# BMduino_test.net
KiCad netlist of a schematic drawn in Altium Designer
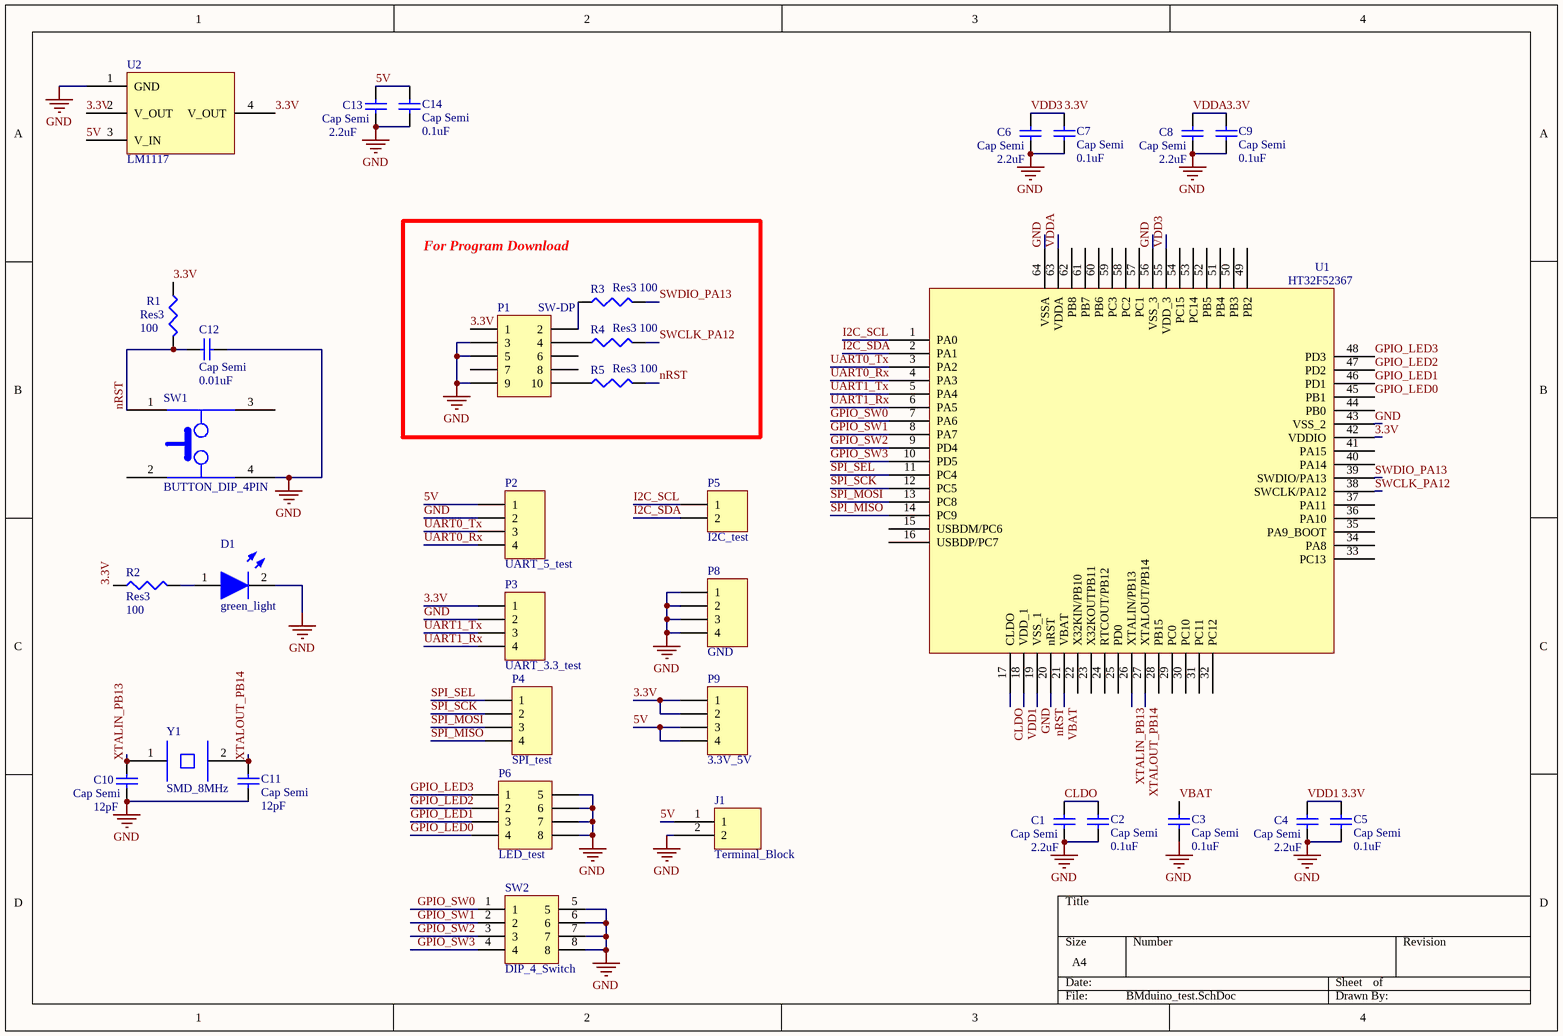
[diagram p0: BMduino_test.SchDoc]

(export (version "E")
  (design (tool "Eeschema 10.0.6"))
  (components
    (comp (ref "C1")
      (value "Cap Semi")
      (footprint "1608[0603]")
      (description "Capacitor (Semiconductor SIM Model)")
      (fields (field (name "ALTIUM_VALUE") "2.2uF") (field (name "PUBLISHER") "Altium Limited"))
      (libsource (lib "Miscellaneous Devices") (part "Cap Semi"))
    )
    (comp (ref "C2")
      (value "Cap Semi")
      (footprint "1608[0603]")
      (description "Capacitor (Semiconductor SIM Model)")
      (fields (field (name "ALTIUM_VALUE") "0.1uF") (field (name "PUBLISHER") "Altium Limited"))
      (libsource (lib "Miscellaneous Devices") (part "Cap Semi"))
    )
    (comp (ref "C3")
      (value "Cap Semi")
      (footprint "1608[0603]")
      (description "Capacitor (Semiconductor SIM Model)")
      (fields (field (name "ALTIUM_VALUE") "0.1uF") (field (name "PUBLISHER") "Altium Limited"))
      (libsource (lib "Miscellaneous Devices") (part "Cap Semi"))
    )
    (comp (ref "C4")
      (value "Cap Semi")
      (footprint "1608[0603]")
      (description "Capacitor (Semiconductor SIM Model)")
      (fields (field (name "ALTIUM_VALUE") "2.2uF") (field (name "PUBLISHER") "Altium Limited"))
      (libsource (lib "Miscellaneous Devices") (part "Cap Semi"))
    )
    (comp (ref "C5")
      (value "Cap Semi")
      (footprint "1608[0603]")
      (description "Capacitor (Semiconductor SIM Model)")
      (fields (field (name "ALTIUM_VALUE") "0.1uF") (field (name "PUBLISHER") "Altium Limited"))
      (libsource (lib "Miscellaneous Devices") (part "Cap Semi"))
    )
    (comp (ref "C6")
      (value "Cap Semi")
      (footprint "1608[0603]")
      (description "Capacitor (Semiconductor SIM Model)")
      (fields (field (name "ALTIUM_VALUE") "2.2uF") (field (name "PUBLISHER") "Altium Limited"))
      (libsource (lib "Miscellaneous Devices") (part "Cap Semi"))
    )
    (comp (ref "C7")
      (value "Cap Semi")
      (footprint "1608[0603]")
      (description "Capacitor (Semiconductor SIM Model)")
      (fields (field (name "ALTIUM_VALUE") "0.1uF") (field (name "PUBLISHER") "Altium Limited"))
      (libsource (lib "Miscellaneous Devices") (part "Cap Semi"))
    )
    (comp (ref "C8")
      (value "Cap Semi")
      (footprint "1608[0603]")
      (description "Capacitor (Semiconductor SIM Model)")
      (fields (field (name "ALTIUM_VALUE") "2.2uF") (field (name "PUBLISHER") "Altium Limited"))
      (libsource (lib "Miscellaneous Devices") (part "Cap Semi"))
    )
    (comp (ref "C9")
      (value "Cap Semi")
      (footprint "1608[0603]")
      (description "Capacitor (Semiconductor SIM Model)")
      (fields (field (name "ALTIUM_VALUE") "0.1uF") (field (name "PUBLISHER") "Altium Limited"))
      (libsource (lib "Miscellaneous Devices") (part "Cap Semi"))
    )
    (comp (ref "C10")
      (value "Cap Semi")
      (footprint "1608[0603]")
      (description "Capacitor (Semiconductor SIM Model)")
      (fields (field (name "ALTIUM_VALUE") "12pF") (field (name "PUBLISHER") "Altium Limited"))
      (libsource (lib "Miscellaneous Devices") (part "Cap Semi"))
    )
    (comp (ref "C11")
      (value "Cap Semi")
      (footprint "1608[0603]")
      (description "Capacitor (Semiconductor SIM Model)")
      (fields (field (name "ALTIUM_VALUE") "12pF") (field (name "PUBLISHER") "Altium Limited"))
      (libsource (lib "Miscellaneous Devices") (part "Cap Semi"))
    )
    (comp (ref "C12")
      (value "Cap Semi")
      (footprint "1608[0603]")
      (description "Capacitor (Semiconductor SIM Model)")
      (fields (field (name "ALTIUM_VALUE") "0.01uF") (field (name "PUBLISHER") "Altium Limited"))
      (libsource (lib "Miscellaneous Devices") (part "Cap Semi"))
    )
    (comp (ref "C13")
      (value "Cap Semi")
      (footprint "1608[0603]")
      (description "Capacitor (Semiconductor SIM Model)")
      (fields (field (name "ALTIUM_VALUE") "2.2uF") (field (name "PUBLISHER") "Altium Limited"))
      (libsource (lib "Miscellaneous Devices") (part "Cap Semi"))
    )
    (comp (ref "C14")
      (value "Cap Semi")
      (footprint "1608[0603]")
      (description "Capacitor (Semiconductor SIM Model)")
      (fields (field (name "ALTIUM_VALUE") "0.1uF") (field (name "PUBLISHER") "Altium Limited"))
      (libsource (lib "Miscellaneous Devices") (part "Cap Semi"))
    )
    (comp (ref "D1")
      (value "green_light")
      (footprint "LED_Green")
      (libsource (lib "Lab_share") (part "LED_Green"))
    )
    (comp (ref "J1")
      (value "Terminal_Block")
      (footprint "terminal block")
      (libsource (lib "Lab_share") (part "Terminal Block"))
    )
    (comp (ref "P1")
      (value "SW-DP")
      (footprint "HDR2X5")
      (description "Header, 5-Pin, Dual row")
      (fields (field (name "PUBLISHER") "Altium Limited"))
      (libsource (lib "Miscellaneous Connectors") (part "Header 5X2"))
    )
    (comp (ref "P2")
      (value "UART_5_test")
      (footprint "HDR1X4")
      (description "Header, 4-Pin")
      (fields (field (name "PUBLISHER") "Altium Limited"))
      (libsource (lib "Miscellaneous Connectors") (part "Header 4"))
    )
    (comp (ref "P3")
      (value "UART_3.3_test")
      (footprint "HDR1X4")
      (description "Header, 4-Pin")
      (fields (field (name "PUBLISHER") "Altium Limited"))
      (libsource (lib "Miscellaneous Connectors") (part "Header 4"))
    )
    (comp (ref "P4")
      (value "SPI_test")
      (footprint "HDR1X4")
      (description "Header, 4-Pin")
      (fields (field (name "PUBLISHER") "Altium Limited"))
      (libsource (lib "Miscellaneous Connectors") (part "Header 4"))
    )
    (comp (ref "P5")
      (value "I2C_test")
      (footprint "HDR1X2")
      (description "Header, 2-Pin")
      (fields (field (name "PUBLISHER") "Altium Limited"))
      (libsource (lib "Miscellaneous Connectors") (part "Header 2"))
    )
    (comp (ref "P6")
      (value "LED_test")
      (footprint "HDR2X4_CEN")
      (description "Header, 4-Pin, Dual row")
      (fields (field (name "PUBLISHER") "Altium Limited"))
      (libsource (lib "Miscellaneous Connectors") (part "Header 4X2A"))
    )
    (comp (ref "P8")
      (value "GND")
      (footprint "HDR1X4")
      (description "Header, 4-Pin")
      (fields (field (name "PUBLISHER") "Altium Limited"))
      (libsource (lib "Miscellaneous Connectors") (part "Header 4"))
    )
    (comp (ref "P9")
      (value "3.3V_5V")
      (footprint "HDR1X4")
      (description "Header, 4-Pin")
      (fields (field (name "PUBLISHER") "Altium Limited"))
      (libsource (lib "Miscellaneous Connectors") (part "Header 4"))
    )
    (comp (ref "R1")
      (value "Res3")
      (footprint "J1-0603")
      (description "Resistor")
      (fields (field (name "ALTIUM_VALUE") "100") (field (name "PUBLISHER") "Altium Limited"))
      (libsource (lib "Miscellaneous Devices") (part "Res3"))
    )
    (comp (ref "R2")
      (value "Res3")
      (footprint "J1-0603")
      (description "Resistor")
      (fields (field (name "ALTIUM_VALUE") "100") (field (name "PUBLISHER") "Altium Limited"))
      (libsource (lib "Miscellaneous Devices") (part "Res3"))
    )
    (comp (ref "R3")
      (value "Res3")
      (footprint "J1-0603")
      (description "Resistor")
      (fields (field (name "ALTIUM_VALUE") "100") (field (name "PUBLISHER") "Altium Limited"))
      (libsource (lib "Miscellaneous Devices") (part "Res3"))
    )
    (comp (ref "R4")
      (value "Res3")
      (footprint "J1-0603")
      (description "Resistor")
      (fields (field (name "ALTIUM_VALUE") "100") (field (name "PUBLISHER") "Altium Limited"))
      (libsource (lib "Miscellaneous Devices") (part "Res3"))
    )
    (comp (ref "R5")
      (value "Res3")
      (footprint "J1-0603")
      (description "Resistor")
      (fields (field (name "ALTIUM_VALUE") "100") (field (name "PUBLISHER") "Altium Limited"))
      (libsource (lib "Miscellaneous Devices") (part "Res3"))
    )
    (comp (ref "SW1")
      (value "BUTTON_DIP_4PIN")
      (footprint "Push_Button")
      (libsource (lib "Lab_share") (part "Push_Button"))
    )
    (comp (ref "SW2")
      (value "DIP_4_Switch")
      (footprint "Switch_4")
      (libsource (lib "Lab_share") (part "Switch_4"))
    )
    (comp (ref "U1")
      (value "HT32F52367")
      (footprint "HT32H52367")
      (libsource (lib "Lab_share") (part "HT32F52367"))
    )
    (comp (ref "U2")
      (value "LM1117")
      (footprint "LM1117 - duplicate")
      (libsource (lib "Lab_share") (part "LM1117"))
    )
    (comp (ref "Y1")
      (value "SMD_8MHz")
      (footprint "Quartz-Crystal-8MHz")
      (libsource (lib "Lab_share") (part "Quartz_Crystal_8MHz"))
    )
  )
  (nets
    (net (code "1") (name "/3.3V") (class "Default")
      (node (ref "C4") (pin "1") (pinfunction "1_1") (pintype "passive"))
      (node (ref "C5") (pin "2") (pinfunction "2_2") (pintype "passive"))
      (node (ref "C6") (pin "1") (pinfunction "1_1") (pintype "passive"))
      (node (ref "C7") (pin "2") (pinfunction "2_2") (pintype "passive"))
      (node (ref "C8") (pin "1") (pinfunction "1_1") (pintype "passive"))
      (node (ref "C9") (pin "2") (pinfunction "2_2") (pintype "passive"))
      (node (ref "P1") (pin "1") (pinfunction "1_1") (pintype "passive"))
      (node (ref "P3") (pin "1") (pinfunction "1_1") (pintype "passive"))
      (node (ref "P9") (pin "1") (pinfunction "1_1") (pintype "passive"))
      (node (ref "P9") (pin "2") (pinfunction "2_2") (pintype "passive"))
      (node (ref "R1") (pin "1") (pinfunction "1_1") (pintype "passive"))
      (node (ref "R2") (pin "1") (pinfunction "1_1") (pintype "passive"))
      (node (ref "U1") (pin "18") (pinfunction "VDD_1_18") (pintype "passive"))
      (node (ref "U1") (pin "42") (pinfunction "VDDIO_42") (pintype "passive"))
      (node (ref "U1") (pin "55") (pinfunction "VDD_3_55") (pintype "passive"))
      (node (ref "U1") (pin "63") (pinfunction "VDDA_63") (pintype "passive"))
      (node (ref "U2") (pin "2") (pinfunction "V_OUT_2") (pintype "passive"))
      (node (ref "U2") (pin "4") (pinfunction "V_OUT_4") (pintype "passive"))
    )
    (net (code "2") (name "/5V") (class "Default")
      (node (ref "C13") (pin "1") (pinfunction "1_1") (pintype "passive"))
      (node (ref "C14") (pin "2") (pinfunction "2_2") (pintype "passive"))
      (node (ref "J1") (pin "1") (pinfunction "1_1") (pintype "passive"))
      (node (ref "P2") (pin "1") (pinfunction "1_1") (pintype "passive"))
      (node (ref "P9") (pin "3") (pinfunction "3_3") (pintype "passive"))
      (node (ref "P9") (pin "4") (pinfunction "4_4") (pintype "passive"))
      (node (ref "U2") (pin "3") (pinfunction "V_IN_3") (pintype "passive"))
    )
    (net (code "3") (name "/CLDO") (class "Default")
      (node (ref "C1") (pin "1") (pinfunction "1_1") (pintype "passive"))
      (node (ref "C2") (pin "2") (pinfunction "2_2") (pintype "passive"))
      (node (ref "U1") (pin "17") (pinfunction "CLDO_17") (pintype "passive"))
    )
    (net (code "4") (name "/GPIO_LED0") (class "Default")
      (node (ref "P6") (pin "4") (pinfunction "4_4") (pintype "passive"))
      (node (ref "U1") (pin "45") (pinfunction "PB1_45") (pintype "passive"))
    )
    (net (code "5") (name "/GPIO_LED1") (class "Default")
      (node (ref "P6") (pin "3") (pinfunction "3_3") (pintype "passive"))
      (node (ref "U1") (pin "46") (pinfunction "PD1_46") (pintype "passive"))
    )
    (net (code "6") (name "/GPIO_LED2") (class "Default")
      (node (ref "P6") (pin "2") (pinfunction "2_2") (pintype "passive"))
      (node (ref "U1") (pin "47") (pinfunction "PD2_47") (pintype "passive"))
    )
    (net (code "7") (name "/GPIO_LED3") (class "Default")
      (node (ref "P6") (pin "1") (pinfunction "1_1") (pintype "passive"))
      (node (ref "U1") (pin "48") (pinfunction "PD3_48") (pintype "passive"))
    )
    (net (code "8") (name "/GPIO_SW0") (class "Default")
      (node (ref "SW2") (pin "1") (pinfunction "1_1") (pintype "passive"))
      (node (ref "U1") (pin "7") (pinfunction "PA6_7") (pintype "passive"))
    )
    (net (code "9") (name "/GPIO_SW1") (class "Default")
      (node (ref "SW2") (pin "2") (pinfunction "2_2") (pintype "passive"))
      (node (ref "U1") (pin "8") (pinfunction "PA7_8") (pintype "passive"))
    )
    (net (code "10") (name "/GPIO_SW2") (class "Default")
      (node (ref "SW2") (pin "3") (pinfunction "3_3") (pintype "passive"))
      (node (ref "U1") (pin "9") (pinfunction "PD4_9") (pintype "passive"))
    )
    (net (code "11") (name "/GPIO_SW3") (class "Default")
      (node (ref "SW2") (pin "4") (pinfunction "4_4") (pintype "passive"))
      (node (ref "U1") (pin "10") (pinfunction "PD5_10") (pintype "passive"))
    )
    (net (code "12") (name "/I2C_SCL") (class "Default")
      (node (ref "P5") (pin "1") (pinfunction "1_1") (pintype "passive"))
      (node (ref "U1") (pin "1") (pinfunction "PA0_1") (pintype "passive"))
    )
    (net (code "13") (name "/I2C_SDA") (class "Default")
      (node (ref "P5") (pin "2") (pinfunction "2_2") (pintype "passive"))
      (node (ref "U1") (pin "2") (pinfunction "PA1_2") (pintype "passive"))
    )
    (net (code "14") (name "/SPI_MISO") (class "Default")
      (node (ref "P4") (pin "4") (pinfunction "4_4") (pintype "passive"))
      (node (ref "U1") (pin "14") (pinfunction "PC9_14") (pintype "passive"))
    )
    (net (code "15") (name "/SPI_MOSI") (class "Default")
      (node (ref "P4") (pin "3") (pinfunction "3_3") (pintype "passive"))
      (node (ref "U1") (pin "13") (pinfunction "PC8_13") (pintype "passive"))
    )
    (net (code "16") (name "/SPI_SCK") (class "Default")
      (node (ref "P4") (pin "2") (pinfunction "2_2") (pintype "passive"))
      (node (ref "U1") (pin "12") (pinfunction "PC5_12") (pintype "passive"))
    )
    (net (code "17") (name "/SPI_SEL") (class "Default")
      (node (ref "P4") (pin "1") (pinfunction "1_1") (pintype "passive"))
      (node (ref "U1") (pin "11") (pinfunction "PC4_11") (pintype "passive"))
    )
    (net (code "18") (name "/SWCLK_PA12") (class "Default")
      (node (ref "R4") (pin "2") (pinfunction "2_2") (pintype "passive"))
      (node (ref "U1") (pin "38") (pinfunction "SWCLK/PA12_38") (pintype "passive"))
    )
    (net (code "19") (name "/SWDIO_PA13") (class "Default")
      (node (ref "R3") (pin "2") (pinfunction "2_2") (pintype "passive"))
      (node (ref "U1") (pin "39") (pinfunction "SWDIO/PA13_39") (pintype "passive"))
    )
    (net (code "20") (name "/UART0_Rx") (class "Default")
      (node (ref "P2") (pin "4") (pinfunction "4_4") (pintype "passive"))
      (node (ref "U1") (pin "4") (pinfunction "PA3_4") (pintype "passive"))
    )
    (net (code "21") (name "/UART0_Tx") (class "Default")
      (node (ref "P2") (pin "3") (pinfunction "3_3") (pintype "passive"))
      (node (ref "U1") (pin "3") (pinfunction "PA2_3") (pintype "passive"))
    )
    (net (code "22") (name "/UART1_Rx") (class "Default")
      (node (ref "P3") (pin "4") (pinfunction "4_4") (pintype "passive"))
      (node (ref "U1") (pin "6") (pinfunction "PA5_6") (pintype "passive"))
    )
    (net (code "23") (name "/UART1_Tx") (class "Default")
      (node (ref "P3") (pin "3") (pinfunction "3_3") (pintype "passive"))
      (node (ref "U1") (pin "5") (pinfunction "PA4_5") (pintype "passive"))
    )
    (net (code "24") (name "/VBAT") (class "Default")
      (node (ref "C3") (pin "2") (pinfunction "2_2") (pintype "passive"))
      (node (ref "U1") (pin "21") (pinfunction "VBAT_21") (pintype "passive"))
    )
    (net (code "25") (name "/XTALIN_PB13") (class "Default")
      (node (ref "C10") (pin "1") (pinfunction "1_1") (pintype "passive"))
      (node (ref "U1") (pin "26") (pinfunction "XTALIN/PB13_26") (pintype "passive"))
      (node (ref "Y1") (pin "1") (pintype "passive"))
    )
    (net (code "26") (name "/XTALOUT_PB14") (class "Default")
      (node (ref "C11") (pin "2") (pinfunction "2_2") (pintype "passive"))
      (node (ref "U1") (pin "27") (pinfunction "XTALOUT/PB14_27") (pintype "passive"))
      (node (ref "Y1") (pin "2") (pintype "passive"))
    )
    (net (code "27") (name "/nRST") (class "Default")
      (node (ref "C12") (pin "2") (pinfunction "2_2") (pintype "passive"))
      (node (ref "R1") (pin "2") (pinfunction "2_2") (pintype "passive"))
      (node (ref "R5") (pin "2") (pinfunction "2_2") (pintype "passive"))
      (node (ref "SW1") (pin "1") (pintype "passive"))
      (node (ref "U1") (pin "20") (pinfunction "nRST_20") (pintype "passive"))
    )
    (net (code "28") (name "GND") (class "Default")
      (node (ref "C1") (pin "2") (pinfunction "2_2") (pintype "passive"))
      (node (ref "C10") (pin "2") (pinfunction "2_2") (pintype "passive"))
      (node (ref "C11") (pin "1") (pinfunction "1_1") (pintype "passive"))
      (node (ref "C12") (pin "1") (pinfunction "1_1") (pintype "passive"))
      (node (ref "C13") (pin "2") (pinfunction "2_2") (pintype "passive"))
      (node (ref "C14") (pin "1") (pinfunction "1_1") (pintype "passive"))
      (node (ref "C2") (pin "1") (pinfunction "1_1") (pintype "passive"))
      (node (ref "C3") (pin "1") (pinfunction "1_1") (pintype "passive"))
      (node (ref "C4") (pin "2") (pinfunction "2_2") (pintype "passive"))
      (node (ref "C5") (pin "1") (pinfunction "1_1") (pintype "passive"))
      (node (ref "C6") (pin "2") (pinfunction "2_2") (pintype "passive"))
      (node (ref "C7") (pin "1") (pinfunction "1_1") (pintype "passive"))
      (node (ref "C8") (pin "2") (pinfunction "2_2") (pintype "passive"))
      (node (ref "C9") (pin "1") (pinfunction "1_1") (pintype "passive"))
      (node (ref "D1") (pin "2") (pintype "passive"))
      (node (ref "J1") (pin "2") (pinfunction "2_2") (pintype "passive"))
      (node (ref "P1") (pin "3") (pinfunction "3_3") (pintype "passive"))
      (node (ref "P1") (pin "5") (pinfunction "5_5") (pintype "passive"))
      (node (ref "P1") (pin "9") (pinfunction "9_9") (pintype "passive"))
      (node (ref "P2") (pin "2") (pinfunction "2_2") (pintype "passive"))
      (node (ref "P3") (pin "2") (pinfunction "2_2") (pintype "passive"))
      (node (ref "P6") (pin "5") (pinfunction "5_5") (pintype "passive"))
      (node (ref "P6") (pin "6") (pinfunction "6_6") (pintype "passive"))
      (node (ref "P6") (pin "7") (pinfunction "7_7") (pintype "passive"))
      (node (ref "P6") (pin "8") (pinfunction "8_8") (pintype "passive"))
      (node (ref "P8") (pin "1") (pinfunction "1_1") (pintype "passive"))
      (node (ref "P8") (pin "2") (pinfunction "2_2") (pintype "passive"))
      (node (ref "P8") (pin "3") (pinfunction "3_3") (pintype "passive"))
      (node (ref "P8") (pin "4") (pinfunction "4_4") (pintype "passive"))
      (node (ref "SW1") (pin "4") (pintype "passive"))
      (node (ref "SW2") (pin "5") (pinfunction "5_5") (pintype "passive"))
      (node (ref "SW2") (pin "6") (pinfunction "6_6") (pintype "passive"))
      (node (ref "SW2") (pin "7") (pinfunction "7_7") (pintype "passive"))
      (node (ref "SW2") (pin "8") (pinfunction "8_8") (pintype "passive"))
      (node (ref "U1") (pin "19") (pinfunction "VSS_1_19") (pintype "passive"))
      (node (ref "U1") (pin "43") (pinfunction "VSS_2_43") (pintype "passive"))
      (node (ref "U1") (pin "56") (pinfunction "VSS_3_56") (pintype "passive"))
      (node (ref "U1") (pin "64") (pinfunction "VSSA_64") (pintype "passive"))
      (node (ref "U2") (pin "1") (pinfunction "GND_1") (pintype "passive"))
    )
    (net (code "29") (name "Net-(D1-Pad1)") (class "Default")
      (node (ref "D1") (pin "1") (pintype "passive"))
      (node (ref "R2") (pin "2") (pinfunction "2_2") (pintype "passive"))
    )
    (net (code "30") (name "Net-(P1-Pad2)") (class "Default")
      (node (ref "P1") (pin "2") (pinfunction "2_2") (pintype "passive"))
      (node (ref "R3") (pin "1") (pinfunction "1_1") (pintype "passive"))
    )
    (net (code "31") (name "Net-(P1-Pad4)") (class "Default")
      (node (ref "P1") (pin "4") (pinfunction "4_4") (pintype "passive"))
      (node (ref "R4") (pin "1") (pinfunction "1_1") (pintype "passive"))
    )
    (net (code "32") (name "Net-(P1-Pad10)") (class "Default")
      (node (ref "P1") (pin "10") (pinfunction "10_10") (pintype "passive"))
      (node (ref "R5") (pin "1") (pinfunction "1_1") (pintype "passive"))
    )
    (net (code "33") (name "unconnected-(P1-Pad6)") (class "Default")
      (node (ref "P1") (pin "6") (pinfunction "6_6") (pintype "passive"))
    )
    (net (code "34") (name "unconnected-(P1-Pad7)") (class "Default")
      (node (ref "P1") (pin "7") (pinfunction "7_7") (pintype "passive"))
    )
    (net (code "35") (name "unconnected-(P1-Pad8)") (class "Default")
      (node (ref "P1") (pin "8") (pinfunction "8_8") (pintype "passive"))
    )
    (net (code "36") (name "unconnected-(SW1-Pad2)") (class "Default")
      (node (ref "SW1") (pin "2") (pintype "passive"))
    )
    (net (code "37") (name "unconnected-(SW1-Pad3)") (class "Default")
      (node (ref "SW1") (pin "3") (pintype "passive"))
    )
    (net (code "38") (name "unconnected-(U1-PA8-Pad34)") (class "Default")
      (node (ref "U1") (pin "34") (pinfunction "PA8_34") (pintype "passive"))
    )
    (net (code "39") (name "unconnected-(U1-PA9_BOOT-Pad35)") (class "Default")
      (node (ref "U1") (pin "35") (pinfunction "PA9_BOOT_35") (pintype "passive"))
    )
    (net (code "40") (name "unconnected-(U1-PA10-Pad36)") (class "Default")
      (node (ref "U1") (pin "36") (pinfunction "PA10_36") (pintype "passive"))
    )
    (net (code "41") (name "unconnected-(U1-PA11-Pad37)") (class "Default")
      (node (ref "U1") (pin "37") (pinfunction "PA11_37") (pintype "passive"))
    )
    (net (code "42") (name "unconnected-(U1-PA14-Pad40)") (class "Default")
      (node (ref "U1") (pin "40") (pinfunction "PA14_40") (pintype "passive"))
    )
    (net (code "43") (name "unconnected-(U1-PA15-Pad41)") (class "Default")
      (node (ref "U1") (pin "41") (pinfunction "PA15_41") (pintype "passive"))
    )
    (net (code "44") (name "unconnected-(U1-PB0-Pad44)") (class "Default")
      (node (ref "U1") (pin "44") (pinfunction "PB0_44") (pintype "passive"))
    )
    (net (code "45") (name "unconnected-(U1-PB2-Pad49)") (class "Default")
      (node (ref "U1") (pin "49") (pinfunction "PB2_49") (pintype "passive"))
    )
    (net (code "46") (name "unconnected-(U1-PB3-Pad50)") (class "Default")
      (node (ref "U1") (pin "50") (pinfunction "PB3_50") (pintype "passive"))
    )
    (net (code "47") (name "unconnected-(U1-PB4-Pad51)") (class "Default")
      (node (ref "U1") (pin "51") (pinfunction "PB4_51") (pintype "passive"))
    )
    (net (code "48") (name "unconnected-(U1-PB5-Pad52)") (class "Default")
      (node (ref "U1") (pin "52") (pinfunction "PB5_52") (pintype "passive"))
    )
    (net (code "49") (name "unconnected-(U1-PB6-Pad60)") (class "Default")
      (node (ref "U1") (pin "60") (pinfunction "PB6_60") (pintype "passive"))
    )
    (net (code "50") (name "unconnected-(U1-PB7-Pad61)") (class "Default")
      (node (ref "U1") (pin "61") (pinfunction "PB7_61") (pintype "passive"))
    )
    (net (code "51") (name "unconnected-(U1-PB8-Pad62)") (class "Default")
      (node (ref "U1") (pin "62") (pinfunction "PB8_62") (pintype "passive"))
    )
    (net (code "52") (name "unconnected-(U1-PB15-Pad28)") (class "Default")
      (node (ref "U1") (pin "28") (pinfunction "PB15_28") (pintype "passive"))
    )
    (net (code "53") (name "unconnected-(U1-PC0-Pad29)") (class "Default")
      (node (ref "U1") (pin "29") (pinfunction "PC0_29") (pintype "passive"))
    )
    (net (code "54") (name "unconnected-(U1-PC1-Pad57)") (class "Default")
      (node (ref "U1") (pin "57") (pinfunction "PC1_57") (pintype "passive"))
    )
    (net (code "55") (name "unconnected-(U1-PC2-Pad58)") (class "Default")
      (node (ref "U1") (pin "58") (pinfunction "PC2_58") (pintype "passive"))
    )
    (net (code "56") (name "unconnected-(U1-PC3-Pad59)") (class "Default")
      (node (ref "U1") (pin "59") (pinfunction "PC3_59") (pintype "passive"))
    )
    (net (code "57") (name "unconnected-(U1-PC10-Pad30)") (class "Default")
      (node (ref "U1") (pin "30") (pinfunction "PC10_30") (pintype "passive"))
    )
    (net (code "58") (name "unconnected-(U1-PC11-Pad31)") (class "Default")
      (node (ref "U1") (pin "31") (pinfunction "PC11_31") (pintype "passive"))
    )
    (net (code "59") (name "unconnected-(U1-PC12-Pad32)") (class "Default")
      (node (ref "U1") (pin "32") (pinfunction "PC12_32") (pintype "passive"))
    )
    (net (code "60") (name "unconnected-(U1-PC13-Pad33)") (class "Default")
      (node (ref "U1") (pin "33") (pinfunction "PC13_33") (pintype "passive"))
    )
    (net (code "61") (name "unconnected-(U1-PC14-Pad53)") (class "Default")
      (node (ref "U1") (pin "53") (pinfunction "PC14_53") (pintype "passive"))
    )
    (net (code "62") (name "unconnected-(U1-PC15-Pad54)") (class "Default")
      (node (ref "U1") (pin "54") (pinfunction "PC15_54") (pintype "passive"))
    )
    (net (code "63") (name "unconnected-(U1-PD0-Pad25)") (class "Default")
      (node (ref "U1") (pin "25") (pinfunction "PD0_25") (pintype "passive"))
    )
    (net (code "64") (name "unconnected-(U1-RTCOUT{slash}PB12-Pad24)") (class "Default")
      (node (ref "U1") (pin "24") (pinfunction "RTCOUT/PB12_24") (pintype "passive"))
    )
    (net (code "65") (name "unconnected-(U1-USBDM{slash}PC6-Pad15)") (class "Default")
      (node (ref "U1") (pin "15") (pinfunction "USBDM/PC6_15") (pintype "passive"))
    )
    (net (code "66") (name "unconnected-(U1-USBDP{slash}PC7-Pad16)") (class "Default")
      (node (ref "U1") (pin "16") (pinfunction "USBDP/PC7_16") (pintype "passive"))
    )
    (net (code "67") (name "unconnected-(U1-X32KIN{slash}PB10-Pad22)") (class "Default")
      (node (ref "U1") (pin "22") (pinfunction "X32KIN/PB10_22") (pintype "passive"))
    )
    (net (code "68") (name "unconnected-(U1-X32KOUTPB11-Pad23)") (class "Default")
      (node (ref "U1") (pin "23") (pinfunction "X32KOUTPB11_23") (pintype "passive"))
    )
  )
)
